# TIDA-01576_ADS8686S_ISO_Interface_Pg5-Di.net
KiCad netlist of a schematic drawn in Altium Designer
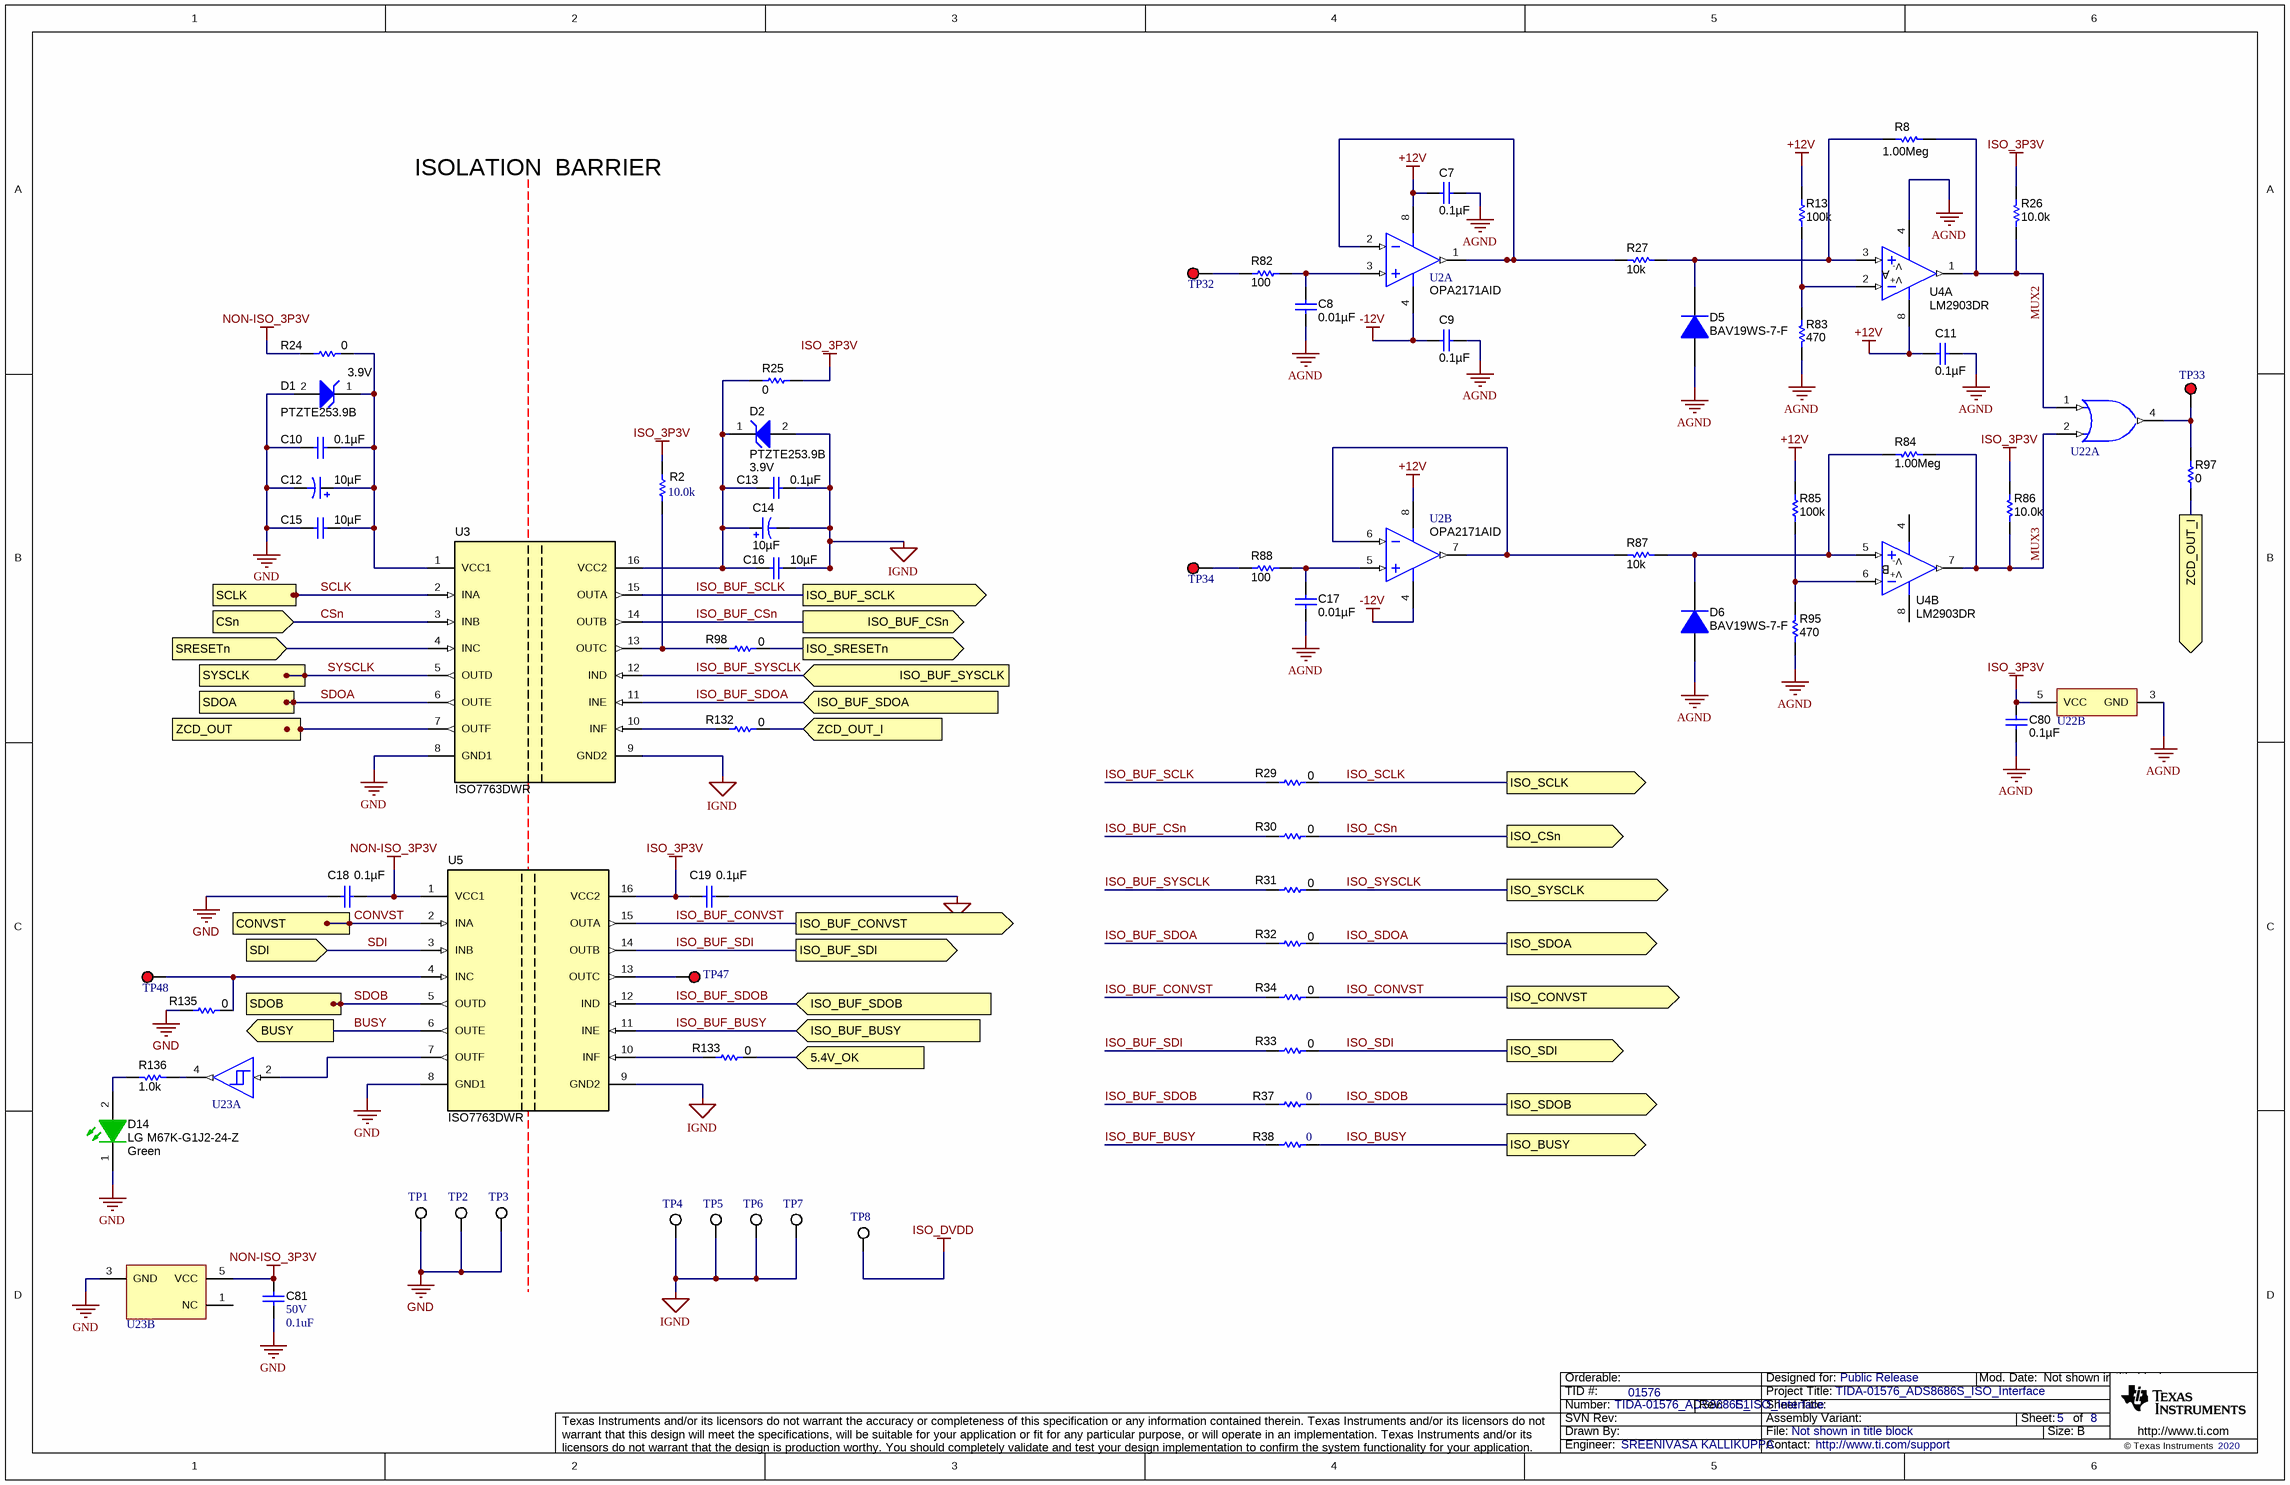
[diagram p0: TIDA-01576_ADS8686S_ISO_Interface_Pg5-Digital.SchDoc]

(export (version "E")
  (design (tool "Eeschema 10.0.6"))
  (components
    (comp (ref "C7")
      (value "06033C104JAT2A")
      (footprint "0603")
      (description "CAP, CERM, 0.1uF, 25V, +/-5%, X7R, 0603")
      (fields
        (field (name "VALUEDISPLAYED") "0.1µF")
        (field (name "MANUFACTURER") "AVX")
        (field (name "PUBLISHER") "Texas Instruments")
      )
      (libsource (lib "Capacitor_Ceramic") (part "06033C104JAT2A"))
    )
    (comp (ref "C8")
      (value "C1608C0G1E103J080AA")
      (footprint "0603")
      (description "CAP, CERM, 0.01uF, 25V, +/-5%, C0G/NP0, 0603")
      (fields
        (field (name "VALUEDISPLAYED") "0.01µF")
        (field (name "MANUFACTURER") "TDK")
        (field (name "PUBLISHER") "Texas Instruments")
      )
      (libsource (lib "Capacitor_Ceramic") (part "C1608C0G1E103J"))
    )
    (comp (ref "C9")
      (value "06033C104JAT2A")
      (footprint "0603")
      (description "CAP, CERM, 0.1uF, 25V, +/-5%, X7R, 0603")
      (fields
        (field (name "VALUEDISPLAYED") "0.1µF")
        (field (name "MANUFACTURER") "AVX")
        (field (name "PUBLISHER") "Texas Instruments")
      )
      (libsource (lib "Capacitor_Ceramic") (part "06033C104JAT2A"))
    )
    (comp (ref "C10")
      (value "C0603C104K5RACTU")
      (footprint "0603")
      (description "CAP, CERM, 0.1uF, 50V, +/-10%, X7R, 0603")
      (fields
        (field (name "VALUEDISPLAYED") "0.1µF")
        (field (name "MANUFACTURER") "Kemet")
        (field (name "PUBLISHER") "Texas Instruments")
      )
      (libsource (lib "Capacitor_Ceramic") (part "C0603C104K5RACTU"))
    )
    (comp (ref "C11")
      (value "06033C104JAT2A")
      (footprint "0603")
      (description "CAP, CERM, 0.1uF, 25V, +/-5%, X7R, 0603")
      (fields
        (field (name "VALUEDISPLAYED") "0.1µF")
        (field (name "MANUFACTURER") "AVX")
        (field (name "PUBLISHER") "Texas Instruments")
      )
      (libsource (lib "Capacitor_Ceramic") (part "06033C104JAT2A"))
    )
    (comp (ref "C12")
      (value "T491B106K016AT")
      (footprint "3528-21")
      (description "CAP, TA, 10 µF, 16 V, +/- 10%, 2 ohm, SMD")
      (fields
        (field (name "MANUFACTURER") "Vishay-Sprague")
        (field (name "VALUEDISPLAYED") "10µF")
        (field (name "PUBLISHER") "Texas Instruments")
      )
      (libsource (lib "") (part "293D106X9016B2TE3_1"))
    )
    (comp (ref "C13")
      (value "C0603C104K5RACTU")
      (footprint "0603")
      (description "CAP, CERM, 0.1uF, 50V, +/-10%, X7R, 0603")
      (fields
        (field (name "VALUEDISPLAYED") "0.1µF")
        (field (name "MANUFACTURER") "Kemet")
        (field (name "PUBLISHER") "Texas Instruments")
      )
      (libsource (lib "Capacitor_Ceramic") (part "C0603C104K5RACTU"))
    )
    (comp (ref "C14")
      (value "T491B106K016AT")
      (footprint "3528-21")
      (description "CAP, TA, 10 µF, 16 V, +/- 10%, 2 ohm, SMD")
      (fields
        (field (name "MANUFACTURER") "Vishay-Sprague")
        (field (name "VALUEDISPLAYED") "10µF")
        (field (name "PUBLISHER") "Texas Instruments")
      )
      (libsource (lib "Combo_Module_TIDA-00170") (part "293D106X9016B2TE3"))
    )
    (comp (ref "C15")
      (value "GRM31CR61H106KA12L")
      (footprint "1206_180")
      (description "CAP, CERM, 10 µF, 50 V, +/- 10%, X5R, 1206")
      (fields
        (field (name "VALUEDISPLAYED") "10µF")
        (field (name "MANUFACTURER") "MuRata")
        (field (name "PUBLISHER") "Texas Instruments")
      )
      (libsource (lib "Capacitor_Ceramic") (part "GRM31CR61H106KA12L"))
    )
    (comp (ref "C16")
      (value "GRM31CR61H106KA12L")
      (footprint "1206_180")
      (description "CAP, CERM, 10 µF, 50 V, +/- 10%, X5R, 1206")
      (fields
        (field (name "VALUEDISPLAYED") "10µF")
        (field (name "MANUFACTURER") "MuRata")
        (field (name "PUBLISHER") "Texas Instruments")
      )
      (libsource (lib "Capacitor_Ceramic") (part "GRM31CR61H106KA12L"))
    )
    (comp (ref "C17")
      (value "C1608C0G1E103J080AA")
      (footprint "0603")
      (description "CAP, CERM, 0.01uF, 25V, +/-5%, C0G/NP0, 0603")
      (fields
        (field (name "VALUEDISPLAYED") "0.01µF")
        (field (name "MANUFACTURER") "TDK")
        (field (name "PUBLISHER") "Texas Instruments")
      )
      (libsource (lib "Capacitor_Ceramic") (part "C1608C0G1E103J"))
    )
    (comp (ref "C18")
      (value "GRM155R71C104KA88D")
      (footprint "0402")
      (description "CAP, CERM, 0.1 µF, 16 V, +/- 10%, X7R, 0402")
      (fields
        (field (name "VALUEDISPLAYED") "0.1µF")
        (field (name "MANUFACTURER") "MuRata")
        (field (name "PUBLISHER") "Texas Instruments")
      )
      (libsource (lib "Capacitor_Ceramic") (part "GRM155R71C104KA88D"))
    )
    (comp (ref "C19")
      (value "GRM155R71C104KA88D")
      (footprint "0402")
      (description "CAP, CERM, 0.1 µF, 16 V, +/- 10%, X7R, 0402")
      (fields
        (field (name "VALUEDISPLAYED") "0.1µF")
        (field (name "MANUFACTURER") "MuRata")
        (field (name "PUBLISHER") "Texas Instruments")
      )
      (libsource (lib "Capacitor_Ceramic") (part "GRM155R71C104KA88D"))
    )
    (comp (ref "C80")
      (value "06033D104KAT2A")
      (footprint "0603")
      (description "CAP, CERM, 0.1 µF, 25 V,+/- 10%, X5R, 0603")
      (fields
        (field (name "VALUEDISPLAYED") "0.1µF")
        (field (name "MANUFACTURER") "AVX")
        (field (name "PUBLISHER") "Texas Instruments")
      )
      (libsource (lib "Capacitor_Ceramic") (part "06033D104KAT2A"))
    )
    (comp (ref "C81")
      (value "C0603C104K5RACTU")
      (footprint "0603")
      (description "CAP, CERM, 0.1 uF, 50 V, +/- 10%, X7R, 0603")
      (fields
        (field (name "MANUFACTURER") "Kemet")
        (field (name "VDC_V") "50V")
        (field (name "VALUEDISPLAYED") "0.1uF")
        (field (name "PUBLISHER") "Texas Instruments")
      )
      (libsource (lib "Altium Vault - TI") (part "Capacitor"))
    )
    (comp (ref "D1")
      (value "PTZTE253.9B")
      (footprint "SMA")
      (description "DIODE ZENER 4.1V 1W PMDS")
      (fields
        (field (name "MANUFACTURER") "Rohm Semiconductor")
        (field (name "ALTIUM_VALUE") "3.9V")
        (field (name "PUBLISHER") "Texas Instruments")
      )
      (libsource (lib "Local library") (part "PTZTE255.6B"))
    )
    (comp (ref "D2")
      (value "PTZTE253.9B")
      (footprint "SMA")
      (description "DIODE ZENER 4.1V 1W PMDS")
      (fields
        (field (name "MANUFACTURER") "Rohm Semiconductor")
        (field (name "ALTIUM_VALUE") "3.9V")
        (field (name "PUBLISHER") "Texas Instruments")
      )
      (libsource (lib "Local library") (part "PTZTE255.6B"))
    )
    (comp (ref "D5")
      (value "BAV19WS-7-F")
      (footprint "SOD-323")
      (description "Diode, Switching, 100 V, 0.2 A, SOD-323")
      (fields (field (name "MANUFACTURER") "Diodes Inc.") (field (name "PUBLISHER") "Texas Instruments"))
      (libsource (lib "Diode") (part "BAV19WS-7-F"))
    )
    (comp (ref "D6")
      (value "BAV19WS-7-F")
      (footprint "SOD-323")
      (description "Diode, Switching, 100 V, 0.2 A, SOD-323")
      (fields (field (name "MANUFACTURER") "Diodes Inc.") (field (name "PUBLISHER") "Texas Instruments"))
      (libsource (lib "Diode") (part "BAV19WS-7-F"))
    )
    (comp (ref "D14")
      (value "LG M67K-G1J2-24-Z")
      (footprint "LG_M67K_Green")
      (description "LED, Green, SMD")
      (fields
        (field (name "ALTIUM_VALUE") "Green")
        (field (name "MANUFACTURER") "OSRAM")
        (field (name "SYMBOLCREATOR") "Altium")
        (field (name "PUBLISHER") "Texas Instruments")
      )
      (libsource (lib "LED") (part "LG M67K-G1J2-24-Z"))
    )
    (comp (ref "R2")
      (value "ERJ-2RKF1002X")
      (footprint "0402")
      (description "RES, 10.0 k, 1%, 0.1 W, 0402")
      (fields
        (field (name "MANUFACTURER") "Panasonic")
        (field (name "VALUEDISPLAYED") "10.0k")
        (field (name "PUBLISHER") "Texas Instruments")
      )
      (libsource (lib "Altium Vault - TI") (part "Resistor"))
    )
    (comp (ref "R8")
      (value "1.00Meg")
      (footprint "0603")
      (description "RES, 1.00Meg ohm, 1%, 0.1W, 0603")
      (fields
        (field (name "PARTNUMBER") "CRCW06031M00FKEA")
        (field (name "MANUFACTURER") "Vishay-Dale")
        (field (name "PUBLISHER") "Texas Instruments")
      )
      (libsource (lib "Resistor_0603") (part "CRCW06031M00FKEA"))
    )
    (comp (ref "R13")
      (value "RC0603FR-07100KL")
      (footprint "0603")
      (description "RES, 100 k, 1%, 0.1 W, 0603")
      (fields
        (field (name "VALUEDISPLAYED") "100k")
        (field (name "MANUFACTURER") "Yageo America")
        (field (name "PUBLISHER") "Texas Instruments")
      )
      (libsource (lib "Resistor_0603") (part "RC0603FR-07100KL"))
    )
    (comp (ref "R24")
      (value "CRCW06030000Z0EA")
      (footprint "0603")
      (description "RES, 0, 5%, 0.1 W, 0603")
      (fields
        (field (name "VALUEDISPLAYED") "0")
        (field (name "MANUFACTURER") "Vishay-Dale")
        (field (name "PUBLISHER") "Texas Instruments")
      )
      (libsource (lib "Resistor_0603") (part "CRCW06030000Z0EA"))
    )
    (comp (ref "R25")
      (value "CRCW06030000Z0EA")
      (footprint "0603")
      (description "RES, 0, 5%, 0.1 W, 0603")
      (fields
        (field (name "VALUEDISPLAYED") "0")
        (field (name "MANUFACTURER") "Vishay-Dale")
        (field (name "PUBLISHER") "Texas Instruments")
      )
      (libsource (lib "Resistor_0603") (part "CRCW06030000Z0EA"))
    )
    (comp (ref "R26")
      (value "10.0k")
      (footprint "0603")
      (description "RES, 10.0k ohm, 1%, 0.1W, 0603")
      (fields
        (field (name "PARTNUMBER") "CRCW060310K0FKEA")
        (field (name "MANUFACTURER") "Vishay-Dale")
        (field (name "PUBLISHER") "Texas Instruments")
      )
      (libsource (lib "Resistor_0603") (part "CRCW060310K0FKEA"))
    )
    (comp (ref "R27")
      (value "10k")
      (footprint "0603")
      (description "RES, 10.0k ohm, 1%, 0.1W, 0603")
      (fields
        (field (name "PARTNUMBER") "CRCW060310K0FKEA")
        (field (name "MANUFACTURER") "Stackpole Electronics Inc")
        (field (name "PUBLISHER") "Texas Instruments")
      )
      (libsource (lib "Resistor_0603") (part "RNCF0603TKY10K0"))
    )
    (comp (ref "R29")
      (value "ERJ-2GE0R00X")
      (footprint "0402")
      (description "RES, 0, 5%, 0.063 W, 0402")
      (fields
        (field (name "VALUEDISPLAYED") "0")
        (field (name "MANUFACTURER") "Panasonic")
        (field (name "PUBLISHER") "Texas Instruments")
      )
      (libsource (lib "Resistor_0402") (part "ERJ-2GE0R00X"))
    )
    (comp (ref "R30")
      (value "ERJ-2GE0R00X")
      (footprint "0402")
      (description "RES, 0, 5%, 0.063 W, 0402")
      (fields
        (field (name "VALUEDISPLAYED") "0")
        (field (name "MANUFACTURER") "Panasonic")
        (field (name "PUBLISHER") "Texas Instruments")
      )
      (libsource (lib "Resistor_0402") (part "ERJ-2GE0R00X"))
    )
    (comp (ref "R31")
      (value "ERJ-2GE0R00X")
      (footprint "0402")
      (description "RES, 0, 5%, 0.063 W, 0402")
      (fields
        (field (name "VALUEDISPLAYED") "0")
        (field (name "MANUFACTURER") "Panasonic")
        (field (name "PUBLISHER") "Texas Instruments")
      )
      (libsource (lib "Resistor_0402") (part "ERJ-2GE0R00X"))
    )
    (comp (ref "R32")
      (value "ERJ-2GE0R00X")
      (footprint "0402")
      (description "RES, 0, 5%, 0.063 W, 0402")
      (fields
        (field (name "VALUEDISPLAYED") "0")
        (field (name "MANUFACTURER") "Panasonic")
        (field (name "PUBLISHER") "Texas Instruments")
      )
      (libsource (lib "Resistor_0402") (part "ERJ-2GE0R00X"))
    )
    (comp (ref "R33")
      (value "ERJ-2GE0R00X")
      (footprint "0402")
      (description "RES, 0, 5%, 0.063 W, 0402")
      (fields
        (field (name "VALUEDISPLAYED") "0")
        (field (name "MANUFACTURER") "Panasonic")
        (field (name "PUBLISHER") "Texas Instruments")
      )
      (libsource (lib "Resistor_0402") (part "ERJ-2GE0R00X"))
    )
    (comp (ref "R34")
      (value "ERJ-2GE0R00X")
      (footprint "0402")
      (description "RES, 0, 5%, 0.063 W, 0402")
      (fields
        (field (name "VALUEDISPLAYED") "0")
        (field (name "MANUFACTURER") "Panasonic")
        (field (name "PUBLISHER") "Texas Instruments")
      )
      (libsource (lib "Resistor_0402") (part "ERJ-2GE0R00X"))
    )
    (comp (ref "R37")
      (value "ERJ-2GE0R00X")
      (footprint "0402")
      (description "RES, 0, 5%, 0.1 W, AEC-Q200 Grade 0, 0402")
      (fields (field (name "MANUFACTURER") "Panasonic") (field (name "VALUEDISPLAYED") "0"))
      (libsource (lib "Altium Vault - TI") (part "Resistor"))
    )
    (comp (ref "R38")
      (value "ERJ-2GE0R00X")
      (footprint "0402")
      (description "RES, 0, 5%, 0.1 W, AEC-Q200 Grade 0, 0402")
      (fields (field (name "MANUFACTURER") "Panasonic") (field (name "VALUEDISPLAYED") "0"))
      (libsource (lib "Altium Vault - TI") (part "Resistor"))
    )
    (comp (ref "R82")
      (value "100")
      (footprint "0603")
      (description "RES, 100 ohm, 1%, 0.1W, 0603")
      (fields
        (field (name "PARTNUMBER") "CRCW0603100RFKEA")
        (field (name "MANUFACTURER") "Vishay-Dale")
        (field (name "PUBLISHER") "Texas Instruments")
      )
      (libsource (lib "Resistor_0603") (part "CRCW0603100RFKEA"))
    )
    (comp (ref "R83")
      (value "RC1206FR-07470RL")
      (footprint "1206")
      (description "RES, 470, 1%, 0.25 W, 1206")
      (fields
        (field (name "MANUFACTURER") "Yageo America")
        (field (name "VALUEDISPLAYED") "470")
        (field (name "PUBLISHER") "Texas Instruments")
      )
      (libsource (lib "Resistor_1206") (part "RC1206FR-07470RL"))
    )
    (comp (ref "R84")
      (value "1.00Meg")
      (footprint "0603")
      (description "RES, 1.00Meg ohm, 1%, 0.1W, 0603")
      (fields
        (field (name "PARTNUMBER") "CRCW06031M00FKEA")
        (field (name "MANUFACTURER") "Vishay-Dale")
        (field (name "PUBLISHER") "Texas Instruments")
      )
      (libsource (lib "Resistor_0603") (part "CRCW06031M00FKEA"))
    )
    (comp (ref "R85")
      (value "RC0603FR-07100KL")
      (footprint "0603")
      (description "RES, 100 k, 1%, 0.1 W, 0603")
      (fields
        (field (name "VALUEDISPLAYED") "100k")
        (field (name "MANUFACTURER") "Yageo America")
        (field (name "PUBLISHER") "Texas Instruments")
      )
      (libsource (lib "Resistor_0603") (part "RC0603FR-07100KL"))
    )
    (comp (ref "R86")
      (value "10.0k")
      (footprint "0603")
      (description "RES, 10.0k ohm, 1%, 0.1W, 0603")
      (fields
        (field (name "PARTNUMBER") "CRCW060310K0FKEA")
        (field (name "MANUFACTURER") "Vishay-Dale")
        (field (name "PUBLISHER") "Texas Instruments")
      )
      (libsource (lib "Resistor_0603") (part "CRCW060310K0FKEA"))
    )
    (comp (ref "R87")
      (value "10k")
      (footprint "0603")
      (description "RES, 10.0k ohm, 1%, 0.1W, 0603")
      (fields
        (field (name "PARTNUMBER") "CRCW060310K0FKEA")
        (field (name "MANUFACTURER") "Stackpole Electronics Inc")
        (field (name "PUBLISHER") "Texas Instruments")
      )
      (libsource (lib "Resistor_0603") (part "RNCF0603TKY10K0"))
    )
    (comp (ref "R88")
      (value "100")
      (footprint "0603")
      (description "RES, 100 ohm, 1%, 0.1W, 0603")
      (fields
        (field (name "PARTNUMBER") "CRCW0603100RFKEA")
        (field (name "MANUFACTURER") "Vishay-Dale")
        (field (name "PUBLISHER") "Texas Instruments")
      )
      (libsource (lib "Resistor_0603") (part "CRCW0603100RFKEA"))
    )
    (comp (ref "R95")
      (value "RC1206FR-07470RL")
      (footprint "1206")
      (description "RES, 470, 1%, 0.25 W, 1206")
      (fields
        (field (name "MANUFACTURER") "Yageo America")
        (field (name "VALUEDISPLAYED") "470")
        (field (name "PUBLISHER") "Texas Instruments")
      )
      (libsource (lib "Resistor_1206") (part "RC1206FR-07470RL"))
    )
    (comp (ref "R97")
      (value "ERJ-2GE0R00X")
      (footprint "0402")
      (description "RES, 0, 5%, 0.063 W, 0402")
      (fields
        (field (name "VALUEDISPLAYED") "0")
        (field (name "MANUFACTURER") "Panasonic")
        (field (name "PUBLISHER") "Texas Instruments")
      )
      (libsource (lib "Resistor_0402") (part "ERJ-2GE0R00X"))
    )
    (comp (ref "R98")
      (value "ERJ-2GE0R00X")
      (footprint "0402")
      (description "RES, 0, 5%, 0.063 W, 0402")
      (fields
        (field (name "VALUEDISPLAYED") "0")
        (field (name "MANUFACTURER") "Panasonic")
        (field (name "PUBLISHER") "Texas Instruments")
      )
      (libsource (lib "Resistor_0402") (part "ERJ-2GE0R00X"))
    )
    (comp (ref "R132")
      (value "ERJ-2GE0R00X")
      (footprint "0402")
      (description "RES, 0, 5%, 0.063 W, 0402")
      (fields
        (field (name "VALUEDISPLAYED") "0")
        (field (name "MANUFACTURER") "Panasonic")
        (field (name "PUBLISHER") "Texas Instruments")
      )
      (libsource (lib "Resistor_0402") (part "ERJ-2GE0R00X"))
    )
    (comp (ref "R133")
      (value "ERJ-2GE0R00X")
      (footprint "0402")
      (description "RES, 0, 5%, 0.063 W, 0402")
      (fields
        (field (name "VALUEDISPLAYED") "0")
        (field (name "MANUFACTURER") "Panasonic")
        (field (name "PUBLISHER") "Texas Instruments")
      )
      (libsource (lib "Resistor_0402") (part "ERJ-2GE0R00X"))
    )
    (comp (ref "R135")
      (value "ERJ-2GE0R00X")
      (footprint "0402")
      (description "RES, 0, 5%, 0.063 W, 0402")
      (fields
        (field (name "VALUEDISPLAYED") "0")
        (field (name "MANUFACTURER") "Panasonic")
        (field (name "PUBLISHER") "Texas Instruments")
      )
      (libsource (lib "Resistor_0402") (part "ERJ-2GE0R00X"))
    )
    (comp (ref "R136")
      (value "RC0603JR-071KL")
      (footprint "0603")
      (description "RES, 1.0 k, 5%, 0.1 W, 0603")
      (fields
        (field (name "VALUEDISPLAYED") "1.0k")
        (field (name "MANUFACTURER") "Yageo America")
        (field (name "PUBLISHER") "Texas Instruments")
      )
      (libsource (lib "Resistor_0603") (part "RC0603JR-071KL"))
    )
    (comp (ref "TP1")
      (value "5015")
      (footprint "Testpoint_Keystone_Miniature")
      (description "Test Point, Miniature, SMT")
      (fields (field (name "MANUFACTURER") "Keystone") (field (name "PUBLISHER") "Texas Instruments"))
      (libsource (lib "Connectors_Keystone") (part "5015"))
    )
    (comp (ref "TP2")
      (value "5015")
      (footprint "Testpoint_Keystone_Miniature")
      (description "Test Point, Miniature, SMT")
      (fields (field (name "MANUFACTURER") "Keystone") (field (name "PUBLISHER") "Texas Instruments"))
      (libsource (lib "Connectors_Keystone") (part "5015"))
    )
    (comp (ref "TP3")
      (value "5015")
      (footprint "Testpoint_Keystone_Miniature")
      (description "Test Point, Miniature, SMT")
      (fields (field (name "MANUFACTURER") "Keystone") (field (name "PUBLISHER") "Texas Instruments"))
      (libsource (lib "Connectors_Keystone") (part "5015"))
    )
    (comp (ref "TP4")
      (value "5015")
      (footprint "Testpoint_Keystone_Miniature")
      (description "Test Point, Miniature, SMT")
      (fields (field (name "MANUFACTURER") "Keystone") (field (name "PUBLISHER") "Texas Instruments"))
      (libsource (lib "Connectors_Keystone") (part "5015"))
    )
    (comp (ref "TP5")
      (value "5015")
      (footprint "Testpoint_Keystone_Miniature")
      (description "Test Point, Miniature, SMT")
      (fields (field (name "MANUFACTURER") "Keystone") (field (name "PUBLISHER") "Texas Instruments"))
      (libsource (lib "Connectors_Keystone") (part "5015"))
    )
    (comp (ref "TP6")
      (value "5015")
      (footprint "Testpoint_Keystone_Miniature")
      (description "Test Point, Miniature, SMT")
      (fields (field (name "MANUFACTURER") "Keystone") (field (name "PUBLISHER") "Texas Instruments"))
      (libsource (lib "Connectors_Keystone") (part "5015"))
    )
    (comp (ref "TP7")
      (value "5015")
      (footprint "Testpoint_Keystone_Miniature")
      (description "Test Point, Miniature, SMT")
      (fields (field (name "MANUFACTURER") "Keystone") (field (name "PUBLISHER") "Texas Instruments"))
      (libsource (lib "Connectors_Keystone") (part "5015"))
    )
    (comp (ref "TP8")
      (value "5015")
      (footprint "Testpoint_Keystone_Miniature")
      (description "Test Point, Miniature, SMT")
      (fields (field (name "MANUFACTURER") "Keystone") (field (name "PUBLISHER") "Texas Instruments"))
      (libsource (lib "Connectors_Keystone") (part "5015"))
    )
    (comp (ref "TP32")
      (value "5000")
      (footprint "Keystone5000")
      (description "Test Point, Miniature, Red, TH")
      (fields (field (name "MANUFACTURER") "Keystone") (field (name "PUBLISHER") "Texas Instruments"))
      (libsource (lib "Connectors_Keystone") (part "5000"))
    )
    (comp (ref "TP33")
      (value "5000")
      (footprint "Keystone5000")
      (description "Test Point, Miniature, Red, TH")
      (fields (field (name "MANUFACTURER") "Keystone") (field (name "PUBLISHER") "Texas Instruments"))
      (libsource (lib "Connectors_Keystone") (part "5000"))
    )
    (comp (ref "TP34")
      (value "5000")
      (footprint "Keystone5000")
      (description "Test Point, Miniature, Red, TH")
      (fields (field (name "MANUFACTURER") "Keystone") (field (name "PUBLISHER") "Texas Instruments"))
      (libsource (lib "Connectors_Keystone") (part "5000"))
    )
    (comp (ref "TP47")
      (value "5000")
      (footprint "Keystone5000")
      (description "Test Point, Miniature, Red, TH")
      (fields (field (name "MANUFACTURER") "Keystone") (field (name "PUBLISHER") "Texas Instruments"))
      (libsource (lib "Connectors_Keystone") (part "5000"))
    )
    (comp (ref "TP48")
      (value "5000")
      (footprint "Keystone5000")
      (description "Test Point, Miniature, Red, TH")
      (fields (field (name "MANUFACTURER") "Keystone") (field (name "PUBLISHER") "Texas Instruments"))
      (libsource (lib "Connectors_Keystone") (part "5000"))
    )
    (comp (ref "U2")
      (value "OPA2171AID")
      (footprint "D0008A_N")
      (fields (field (name "PARTNUMBER") "OPA2171AID") (field (name "MANUFACTURER") "Texas Instruments"))
      (libsource (lib "Altium Vault - TI") (part "TI-OPA-8_2"))
    )
    (comp (ref "U3")
      (value "ISO7763DWR")
      (footprint "DW0016B_HV")
      (description "High Speed, Robust EMC, Reinforced Six-Channel Digital Isolator, DW0016B (SOIC-16)")
      (fields
        (field (name "PARTNUMBER") "ISO7763DWR")
        (field (name "ALTERNATE PARTNUMBER") "ISO7763DW")
        (field (name "MANUFACTURER") "Texas Instruments")
      )
      (libsource (lib "Altium Vault - TI") (part "ISO7763"))
    )
    (comp (ref "U4")
      (value "LM2903DR")
      (footprint "D0008A_N")
      (description "Dual Comparator, D0008A")
      (fields
        (field (name "MANUFACTURER") "Texas Instruments")
        (field (name "PUBLISHER") "Texas Instruments")
      )
      (libsource (lib "NSC Amplifier") (part "LM2903D"))
    )
    (comp (ref "U5")
      (value "ISO7763DWR")
      (footprint "DW0016B_HV")
      (description "High Speed, Robust EMC, Reinforced Six-Channel Digital Isolator, DW0016B (SOIC-16)")
      (fields
        (field (name "PARTNUMBER") "ISO7763DWR")
        (field (name "ALTERNATE PARTNUMBER") "ISO7763DW")
        (field (name "MANUFACTURER") "Texas Instruments")
      )
      (libsource (lib "Altium Vault - TI") (part "ISO7763"))
    )
    (comp (ref "U22")
      (value "SN74LVC1G32DBVR")
      (footprint "DBV0005A_N")
      (description "Single 2-Input Positive-OR Gate, DBV0005A, LARGE T&R")
      (fields (field (name "MANUFACTURER") "Texas Instruments"))
      (libsource (lib "Altium Vault - TI") (part "TI-SN74XXX1X32-5"))
    )
    (comp (ref "U23")
      (value "SN74LVC1G17DCKR")
      (footprint "DCK0005A_N")
      (description "Single Schmitt-Trigger Buffer, DCK0005A, LARGE T&R")
      (fields
        (field (name "MANUFACTURER") "Texas Instruments")
        (field (name "GENERIC PART NUMBER") "SN74LVC1G17")
      )
      (libsource (lib "Altium Vault - TI") (part "TI-SN74XXX1XXX-XX-5-SCHMITT"))
    )
  )
  (nets
    (net (code "1") (name "+12V") (class "Default")
      (node (ref "C11") (pin "2") (pinfunction "2_2") (pintype "passive"))
      (node (ref "C7") (pin "2") (pinfunction "2_2") (pintype "passive"))
      (node (ref "R13") (pin "2") (pinfunction "2_2") (pintype "passive"))
      (node (ref "R85") (pin "2") (pinfunction "2_2") (pintype "passive"))
      (node (ref "U2") (pin "8") (pinfunction "V+_8") (pintype "power_in"))
      (node (ref "U4") (pin "8") (pinfunction "V+_8") (pintype "power_in"))
    )
    (net (code "2") (name "-12V") (class "Default")
      (node (ref "C9") (pin "2") (pinfunction "2_2") (pintype "passive"))
      (node (ref "U2") (pin "4") (pinfunction "V-_4") (pintype "power_in"))
    )
    (net (code "3") (name "/5.4V_OK") (class "Default")
      (node (ref "R133") (pin "2") (pinfunction "2_2") (pintype "passive"))
    )
    (net (code "4") (name "/BUSY") (class "Default")
      (node (ref "U5") (pin "6") (pinfunction "OUTE_6") (pintype "output"))
    )
    (net (code "5") (name "/CONVST") (class "Default")
      (node (ref "U5") (pin "2") (pinfunction "INA_2") (pintype "input"))
    )
    (net (code "6") (name "/CSn") (class "Default")
      (node (ref "U3") (pin "3") (pinfunction "INB_3") (pintype "input"))
    )
    (net (code "7") (name "/ISO_BUF_BUSY") (class "Default")
      (node (ref "R38") (pin "1") (pinfunction "1_1") (pintype "passive"))
      (node (ref "U5") (pin "11") (pinfunction "INE_11") (pintype "input"))
    )
    (net (code "8") (name "/ISO_BUF_CONVST") (class "Default")
      (node (ref "R34") (pin "1") (pinfunction "1_1") (pintype "passive"))
      (node (ref "U5") (pin "15") (pinfunction "OUTA_15") (pintype "output"))
    )
    (net (code "9") (name "/ISO_BUF_CSn") (class "Default")
      (node (ref "R30") (pin "1") (pinfunction "1_1") (pintype "passive"))
      (node (ref "U3") (pin "14") (pinfunction "OUTB_14") (pintype "output"))
    )
    (net (code "10") (name "/ISO_BUF_SCLK") (class "Default")
      (node (ref "R29") (pin "1") (pinfunction "1_1") (pintype "passive"))
      (node (ref "U3") (pin "15") (pinfunction "OUTA_15") (pintype "output"))
    )
    (net (code "11") (name "/ISO_BUF_SDI") (class "Default")
      (node (ref "R33") (pin "1") (pinfunction "1_1") (pintype "passive"))
      (node (ref "U5") (pin "14") (pinfunction "OUTB_14") (pintype "output"))
    )
    (net (code "12") (name "/ISO_BUF_SDOA") (class "Default")
      (node (ref "R32") (pin "1") (pinfunction "1_1") (pintype "passive"))
      (node (ref "U3") (pin "11") (pinfunction "INE_11") (pintype "input"))
    )
    (net (code "13") (name "/ISO_BUF_SDOB") (class "Default")
      (node (ref "R37") (pin "1") (pinfunction "1_1") (pintype "passive"))
      (node (ref "U5") (pin "12") (pinfunction "IND_12") (pintype "input"))
    )
    (net (code "14") (name "/ISO_BUF_SYSCLK") (class "Default")
      (node (ref "R31") (pin "1") (pinfunction "1_1") (pintype "passive"))
      (node (ref "U3") (pin "12") (pinfunction "IND_12") (pintype "input"))
    )
    (net (code "15") (name "/ISO_BUSY") (class "Default")
      (node (ref "R38") (pin "2") (pinfunction "2_2") (pintype "passive"))
    )
    (net (code "16") (name "/ISO_CONVST") (class "Default")
      (node (ref "R34") (pin "2") (pinfunction "2_2") (pintype "passive"))
    )
    (net (code "17") (name "/ISO_CSn") (class "Default")
      (node (ref "R30") (pin "2") (pinfunction "2_2") (pintype "passive"))
    )
    (net (code "18") (name "/ISO_SCLK") (class "Default")
      (node (ref "R29") (pin "2") (pinfunction "2_2") (pintype "passive"))
    )
    (net (code "19") (name "/ISO_SDI") (class "Default")
      (node (ref "R33") (pin "2") (pinfunction "2_2") (pintype "passive"))
    )
    (net (code "20") (name "/ISO_SDOA") (class "Default")
      (node (ref "R32") (pin "2") (pinfunction "2_2") (pintype "passive"))
    )
    (net (code "21") (name "/ISO_SDOB") (class "Default")
      (node (ref "R37") (pin "2") (pinfunction "2_2") (pintype "passive"))
    )
    (net (code "22") (name "/ISO_SRESETn") (class "Default")
      (node (ref "R98") (pin "2") (pinfunction "2_2") (pintype "passive"))
    )
    (net (code "23") (name "/ISO_SYSCLK") (class "Default")
      (node (ref "R31") (pin "2") (pinfunction "2_2") (pintype "passive"))
    )
    (net (code "24") (name "/MUX2") (class "Default")
      (node (ref "R26") (pin "1") (pinfunction "1_1") (pintype "passive"))
      (node (ref "R8") (pin "1") (pinfunction "1_1") (pintype "passive"))
      (node (ref "U22") (pin "1") (pinfunction "A_1") (pintype "input"))
      (node (ref "U4") (pin "1") (pinfunction "OUT_1") (pintype "output"))
    )
    (net (code "25") (name "/MUX3") (class "Default")
      (node (ref "R84") (pin "1") (pinfunction "1_1") (pintype "passive"))
      (node (ref "R86") (pin "1") (pinfunction "1_1") (pintype "passive"))
      (node (ref "U22") (pin "2") (pinfunction "B_2") (pintype "input"))
      (node (ref "U4") (pin "7") (pinfunction "OUT_7") (pintype "output"))
    )
    (net (code "26") (name "/SCLK") (class "Default")
      (node (ref "U3") (pin "2") (pinfunction "INA_2") (pintype "input"))
    )
    (net (code "27") (name "/SDI") (class "Default")
      (node (ref "U5") (pin "3") (pinfunction "INB_3") (pintype "input"))
    )
    (net (code "28") (name "/SDOA") (class "Default")
      (node (ref "U3") (pin "6") (pinfunction "OUTE_6") (pintype "output"))
    )
    (net (code "29") (name "/SDOB") (class "Default")
      (node (ref "U5") (pin "5") (pinfunction "OUTD_5") (pintype "output"))
    )
    (net (code "30") (name "/SRESETn") (class "Default")
      (node (ref "U3") (pin "4") (pinfunction "INC_4") (pintype "input"))
    )
    (net (code "31") (name "/SYSCLK") (class "Default")
      (node (ref "U3") (pin "5") (pinfunction "OUTD_5") (pintype "output"))
    )
    (net (code "32") (name "/ZCD_OUT") (class "Default")
      (node (ref "U3") (pin "7") (pinfunction "OUTF_7") (pintype "output"))
    )
    (net (code "33") (name "/ZCD_OUT_I") (class "Default")
      (node (ref "R132") (pin "2") (pinfunction "2_2") (pintype "passive"))
      (node (ref "R97") (pin "1") (pinfunction "1_1") (pintype "passive"))
    )
    (net (code "34") (name "AGND") (class "Default")
      (node (ref "C11") (pin "1") (pinfunction "1_1") (pintype "passive"))
      (node (ref "C17") (pin "1") (pinfunction "1_1") (pintype "passive"))
      (node (ref "C7") (pin "1") (pinfunction "1_1") (pintype "passive"))
      (node (ref "C8") (pin "1") (pinfunction "1_1") (pintype "passive"))
      (node (ref "C80") (pin "2") (pinfunction "2_2") (pintype "passive"))
      (node (ref "C9") (pin "1") (pinfunction "1_1") (pintype "passive"))
      (node (ref "D5") (pin "2") (pinfunction "A_2") (pintype "passive"))
      (node (ref "D6") (pin "2") (pinfunction "A_2") (pintype "passive"))
      (node (ref "R83") (pin "1") (pinfunction "1_1") (pintype "passive"))
      (node (ref "R95") (pin "1") (pinfunction "1_1") (pintype "passive"))
      (node (ref "U22") (pin "3") (pinfunction "GND_3") (pintype "power_in"))
      (node (ref "U4") (pin "4") (pinfunction "V-_4") (pintype "power_in"))
    )
    (net (code "35") (name "GND") (class "Default")
      (node (ref "C10") (pin "2") (pinfunction "2_2") (pintype "passive"))
      (node (ref "C12") (pin "2") (pinfunction "-_2") (pintype "passive"))
      (node (ref "C15") (pin "2") (pinfunction "2_2") (pintype "passive"))
      (node (ref "C18") (pin "1") (pinfunction "1_1") (pintype "passive"))
      (node (ref "C81") (pin "2") (pinfunction "2_2") (pintype "passive"))
      (node (ref "D1") (pin "2") (pinfunction "A_2") (pintype "passive"))
      (node (ref "D14") (pin "1") (pinfunction "K_1") (pintype "passive"))
      (node (ref "R135") (pin "1") (pinfunction "1_1") (pintype "passive"))
      (node (ref "TP1") (pin "1") (pintype "passive"))
      (node (ref "TP2") (pin "1") (pintype "passive"))
      (node (ref "TP3") (pin "1") (pintype "passive"))
      (node (ref "U23") (pin "3") (pinfunction "GND_3") (pintype "power_in"))
      (node (ref "U3") (pin "8") (pinfunction "GND1_8") (pintype "power_in"))
      (node (ref "U5") (pin "8") (pinfunction "GND1_8") (pintype "power_in"))
    )
    (net (code "36") (name "IGND") (class "Default")
      (node (ref "C13") (pin "2") (pinfunction "2_2") (pintype "passive"))
      (node (ref "C14") (pin "2") (pinfunction "-_2") (pintype "passive"))
      (node (ref "C16") (pin "1") (pinfunction "1_1") (pintype "passive"))
      (node (ref "C19") (pin "2") (pinfunction "2_2") (pintype "passive"))
      (node (ref "D2") (pin "2") (pinfunction "A_2") (pintype "passive"))
      (node (ref "TP4") (pin "1") (pintype "passive"))
      (node (ref "TP5") (pin "1") (pintype "passive"))
      (node (ref "TP6") (pin "1") (pintype "passive"))
      (node (ref "TP7") (pin "1") (pintype "passive"))
      (node (ref "U3") (pin "9") (pinfunction "GND2_9") (pintype "power_in"))
      (node (ref "U5") (pin "9") (pinfunction "GND2_9") (pintype "power_in"))
    )
    (net (code "37") (name "ISO_3P3V") (class "Default")
      (node (ref "C19") (pin "1") (pinfunction "1_1") (pintype "passive"))
      (node (ref "C80") (pin "1") (pinfunction "1_1") (pintype "passive"))
      (node (ref "R2") (pin "2") (pinfunction "2_2") (pintype "passive"))
      (node (ref "R25") (pin "1") (pinfunction "1_1") (pintype "passive"))
      (node (ref "R26") (pin "2") (pinfunction "2_2") (pintype "passive"))
      (node (ref "R86") (pin "2") (pinfunction "2_2") (pintype "passive"))
      (node (ref "U22") (pin "5") (pinfunction "VCC_5") (pintype "power_in"))
      (node (ref "U5") (pin "16") (pinfunction "VCC2_16") (pintype "power_in"))
    )
    (net (code "38") (name "ISO_DVDD") (class "Default") (node (ref "TP8") (pin "1") (pintype "passive")))
    (net (code "39") (name "NON-ISO_3P3V") (class "Default")
      (node (ref "C18") (pin "2") (pinfunction "2_2") (pintype "passive"))
      (node (ref "C81") (pin "1") (pinfunction "1_1") (pintype "passive"))
      (node (ref "R24") (pin "2") (pinfunction "2_2") (pintype "passive"))
      (node (ref "U23") (pin "5") (pinfunction "VCC_5") (pintype "power_in"))
      (node (ref "U5") (pin "1") (pinfunction "VCC1_1") (pintype "power_in"))
    )
    (net (code "40") (name "Net-(C12-+)") (class "Default")
      (node (ref "C10") (pin "1") (pinfunction "1_1") (pintype "passive"))
      (node (ref "C12") (pin "1") (pinfunction "+_1") (pintype "passive"))
      (node (ref "C15") (pin "1") (pinfunction "1_1") (pintype "passive"))
      (node (ref "D1") (pin "1") (pinfunction "K_1") (pintype "passive"))
      (node (ref "R24") (pin "1") (pinfunction "1_1") (pintype "passive"))
      (node (ref "U3") (pin "1") (pinfunction "VCC1_1") (pintype "power_in"))
    )
    (net (code "41") (name "Net-(C14-+)") (class "Default")
      (node (ref "C13") (pin "1") (pinfunction "1_1") (pintype "passive"))
      (node (ref "C14") (pin "1") (pinfunction "+_1") (pintype "passive"))
      (node (ref "C16") (pin "2") (pinfunction "2_2") (pintype "passive"))
      (node (ref "D2") (pin "1") (pinfunction "K_1") (pintype "passive"))
      (node (ref "R25") (pin "2") (pinfunction "2_2") (pintype "passive"))
      (node (ref "U3") (pin "16") (pinfunction "VCC2_16") (pintype "power_in"))
    )
    (net (code "42") (name "Net-(D5-K)") (class "Default")
      (node (ref "D5") (pin "1") (pinfunction "K_1") (pintype "passive"))
      (node (ref "R27") (pin "2") (pinfunction "2_2") (pintype "passive"))
      (node (ref "R8") (pin "2") (pinfunction "2_2") (pintype "passive"))
      (node (ref "U4") (pin "3") (pinfunction "IN+_3") (pintype "input"))
    )
    (net (code "43") (name "Net-(D6-K)") (class "Default")
      (node (ref "D6") (pin "1") (pinfunction "K_1") (pintype "passive"))
      (node (ref "R84") (pin "2") (pinfunction "2_2") (pintype "passive"))
      (node (ref "R87") (pin "2") (pinfunction "2_2") (pintype "passive"))
      (node (ref "U4") (pin "5") (pinfunction "IN+_5") (pintype "input"))
    )
    (net (code "44") (name "Net-(D14-A)") (class "Default")
      (node (ref "D14") (pin "2") (pinfunction "A_2") (pintype "passive"))
      (node (ref "R136") (pin "2") (pinfunction "2_2") (pintype "passive"))
    )
    (net (code "45") (name "Net-(R82-Pad1)") (class "Default")
      (node (ref "R82") (pin "1") (pinfunction "1_1") (pintype "passive"))
      (node (ref "TP32") (pin "1") (pintype "passive"))
    )
    (net (code "46") (name "Net-(R88-Pad1)") (class "Default")
      (node (ref "R88") (pin "1") (pinfunction "1_1") (pintype "passive"))
      (node (ref "TP34") (pin "1") (pintype "passive"))
    )
    (net (code "47") (name "Net-(U2A-IN_A+)") (class "Default")
      (node (ref "C8") (pin "2") (pinfunction "2_2") (pintype "passive"))
      (node (ref "R82") (pin "2") (pinfunction "2_2") (pintype "passive"))
      (node (ref "U2") (pin "3") (pinfunction "IN_A+_3") (pintype "input"))
    )
    (net (code "48") (name "Net-(U2A-IN_A-)") (class "Default")
      (node (ref "R27") (pin "1") (pinfunction "1_1") (pintype "passive"))
      (node (ref "U2") (pin "1") (pinfunction "OUT_A_1") (pintype "output"))
      (node (ref "U2") (pin "2") (pinfunction "IN_A-_2") (pintype "input"))
    )
    (net (code "49") (name "Net-(U2B-IN_B+)") (class "Default")
      (node (ref "C17") (pin "2") (pinfunction "2_2") (pintype "passive"))
      (node (ref "R88") (pin "2") (pinfunction "2_2") (pintype "passive"))
      (node (ref "U2") (pin "5") (pinfunction "IN_B+_5") (pintype "input"))
    )
    (net (code "50") (name "Net-(U2B-IN_B-)") (class "Default")
      (node (ref "R87") (pin "1") (pinfunction "1_1") (pintype "passive"))
      (node (ref "U2") (pin "6") (pinfunction "IN_B-_6") (pintype "input"))
      (node (ref "U2") (pin "7") (pinfunction "OUT_B_7") (pintype "output"))
    )
    (net (code "51") (name "Net-(U3-INF)") (class "Default")
      (node (ref "R132") (pin "1") (pinfunction "1_1") (pintype "passive"))
      (node (ref "U3") (pin "10") (pinfunction "INF_10") (pintype "input"))
    )
    (net (code "52") (name "Net-(U3-OUTC)") (class "Default")
      (node (ref "R2") (pin "1") (pinfunction "1_1") (pintype "passive"))
      (node (ref "R98") (pin "1") (pinfunction "1_1") (pintype "passive"))
      (node (ref "U3") (pin "13") (pinfunction "OUTC_13") (pintype "output"))
    )
    (net (code "53") (name "Net-(U4A-IN-)") (class "Default")
      (node (ref "R13") (pin "1") (pinfunction "1_1") (pintype "passive"))
      (node (ref "R83") (pin "2") (pinfunction "2_2") (pintype "passive"))
      (node (ref "U4") (pin "2") (pinfunction "IN-_2") (pintype "input"))
    )
    (net (code "54") (name "Net-(U4B-IN-)") (class "Default")
      (node (ref "R85") (pin "1") (pinfunction "1_1") (pintype "passive"))
      (node (ref "R95") (pin "2") (pinfunction "2_2") (pintype "passive"))
      (node (ref "U4") (pin "6") (pinfunction "IN-_6") (pintype "input"))
    )
    (net (code "55") (name "Net-(U5-INC)") (class "Default")
      (node (ref "R135") (pin "2") (pinfunction "2_2") (pintype "passive"))
      (node (ref "TP48") (pin "1") (pintype "passive"))
      (node (ref "U5") (pin "4") (pinfunction "INC_4") (pintype "input"))
    )
    (net (code "56") (name "Net-(U5-INF)") (class "Default")
      (node (ref "R133") (pin "1") (pinfunction "1_1") (pintype "passive"))
      (node (ref "U5") (pin "10") (pinfunction "INF_10") (pintype "input"))
    )
    (net (code "57") (name "Net-(U5-OUTC)") (class "Default")
      (node (ref "TP47") (pin "1") (pintype "passive"))
      (node (ref "U5") (pin "13") (pinfunction "OUTC_13") (pintype "output"))
    )
    (net (code "58") (name "Net-(U22A-Y)") (class "Default")
      (node (ref "R97") (pin "2") (pinfunction "2_2") (pintype "passive"))
      (node (ref "TP33") (pin "1") (pintype "passive"))
      (node (ref "U22") (pin "4") (pinfunction "Y_4") (pintype "output"))
    )
    (net (code "59") (name "Net-(U23A-A)") (class "Default")
      (node (ref "U23") (pin "2") (pinfunction "A_2") (pintype "input"))
      (node (ref "U5") (pin "7") (pinfunction "OUTF_7") (pintype "output"))
    )
    (net (code "60") (name "Net-(U23A-Y)") (class "Default")
      (node (ref "R136") (pin "1") (pinfunction "1_1") (pintype "passive"))
      (node (ref "U23") (pin "4") (pinfunction "Y_4") (pintype "output"))
    )
    (net (code "61") (name "unconnected-(U4B-V+-Pad8)") (class "Default")
      (node (ref "U4") (pin "8") (pinfunction "V+_8") (pintype "power_in"))
    )
    (net (code "62") (name "unconnected-(U4B-V--Pad4)") (class "Default")
      (node (ref "U4") (pin "4") (pinfunction "V-_4") (pintype "power_in"))
    )
    (net (code "63") (name "unconnected-(U23B-NC-Pad1)") (class "Default")
      (node (ref "U23") (pin "1") (pinfunction "NC_1") (pintype "passive"))
    )
  )
)
